# MAG.net
KiCad netlist of a schematic drawn in Altium Designer
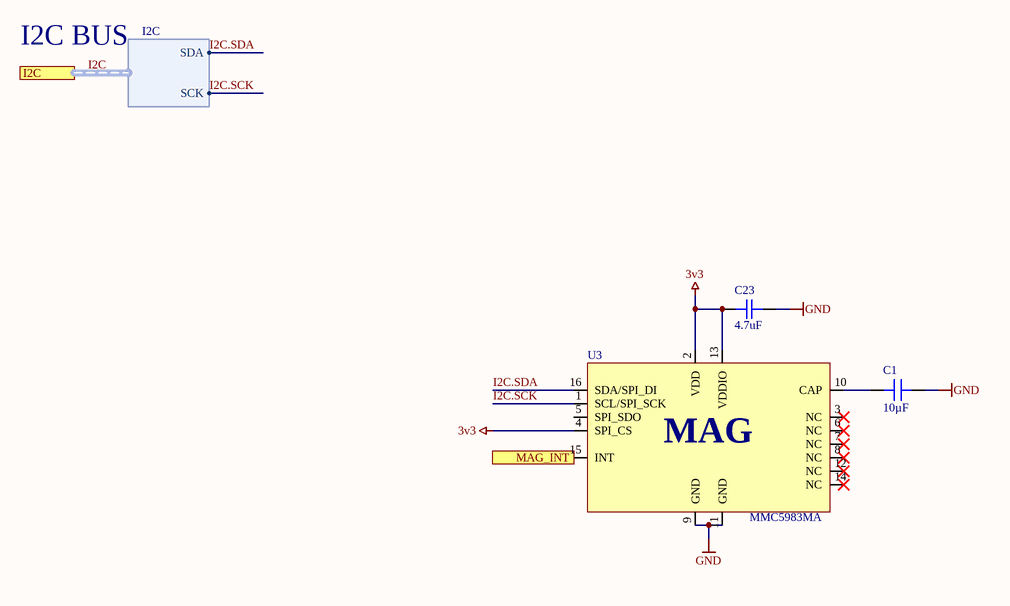
[diagram p0: MAG.SchDoc]

(export (version "E")
  (design (tool "Eeschema 10.0.6"))
  (components
    (comp (ref "C1")
      (value "10µF")
      (footprint "CAP 0603/1608")
      (description "CAP CER 10UF 10V X5R 20% 0603")
      (fields (field (name "TOLERANCE") "20%") (field (name "VOLTAGE") "10V"))
      (libsource (lib "altium-lib") (part "Ceramic_Capacitor"))
    )
    (comp (ref "C23")
      (value "4.7uF")
      (footprint "CAP_0402")
      (description "Capacitor SMD 0402 10V")
      (fields (field (name "Comment") "C0402_10V"))
      (libsource (lib "Schematic-Lib-PhilsLab") (part "CAP_0402_10V"))
    )
    (comp (ref "U3")
      (value "MMC5983MA")
      (footprint "MMC5983MA-LGA")
      (description "±8 Gauss, High Performance 3-axis Magnetic Sensor I2C/SPI")
      (fields (field (name "MANUFACTURER") "MEMSIC"))
      (libsource (lib "Schematic-Lib-PhilsLab") (part "MMC5983MA"))
    )
  )
  (nets
    (net (code "2") (name "/I2C.SCK") (class "Default")
      (node (ref "U3") (pin "1") (pinfunction "SCL/SPI_SCK_1") (pintype "passive"))
    )
    (net (code "3") (name "/I2C.SDA") (class "Default")
      (node (ref "U3") (pin "16") (pinfunction "SDA/SPI_DI_16") (pintype "passive"))
    )
    (net (code "5") (name "/MAG_INT") (class "Default")
      (node (ref "U3") (pin "15") (pinfunction "INT_15") (pintype "passive"))
    )
    (net (code "6") (name "3v3") (class "Default")
      (node (ref "C23") (pin "2") (pinfunction "2_2") (pintype "passive"))
      (node (ref "U3") (pin "13") (pinfunction "VDDIO_13") (pintype "passive"))
      (node (ref "U3") (pin "2") (pinfunction "VDD_2") (pintype "passive"))
      (node (ref "U3") (pin "4") (pinfunction "SPI_CS_4") (pintype "passive"))
    )
    (net (code "7") (name "GND") (class "Default")
      (node (ref "C1") (pin "2") (pinfunction "2_2") (pintype "passive"))
      (node (ref "C23") (pin "1") (pinfunction "1_1") (pintype "passive"))
      (node (ref "U3") (pin "11") (pinfunction "GND_11") (pintype "passive"))
      (node (ref "U3") (pin "9") (pinfunction "GND_9") (pintype "passive"))
    )
    (net (code "8") (name "Net-(U3-CAP)") (class "Default")
      (node (ref "C1") (pin "1") (pinfunction "1_1") (pintype "passive"))
      (node (ref "U3") (pin "10") (pinfunction "CAP_10") (pintype "passive"))
    )
    (net (code "9") (name "unconnected-(U3-NC-Pad3)") (class "Default")
      (node (ref "U3") (pin "3") (pinfunction "NC_3") (pintype "passive+no_connect"))
    )
    (net (code "10") (name "unconnected-(U3-NC-Pad6)") (class "Default")
      (node (ref "U3") (pin "6") (pinfunction "NC_6") (pintype "passive+no_connect"))
    )
    (net (code "11") (name "unconnected-(U3-NC-Pad7)") (class "Default")
      (node (ref "U3") (pin "7") (pinfunction "NC_7") (pintype "passive+no_connect"))
    )
    (net (code "12") (name "unconnected-(U3-NC-Pad8)") (class "Default")
      (node (ref "U3") (pin "8") (pinfunction "NC_8") (pintype "passive+no_connect"))
    )
    (net (code "13") (name "unconnected-(U3-NC-Pad12)") (class "Default")
      (node (ref "U3") (pin "12") (pinfunction "NC_12") (pintype "passive+no_connect"))
    )
    (net (code "14") (name "unconnected-(U3-NC-Pad14)") (class "Default")
      (node (ref "U3") (pin "14") (pinfunction "NC_14") (pintype "passive+no_connect"))
    )
    (net (code "15") (name "unconnected-(U3-SPI_SDO-Pad5)") (class "Default")
      (node (ref "U3") (pin "5") (pinfunction "SPI_SDO_5") (pintype "passive"))
    )
  )
)
